# SCH_Smartlock-V3_2024-05-26.net
KiCad netlist of a schematic drawn in EasyEDA
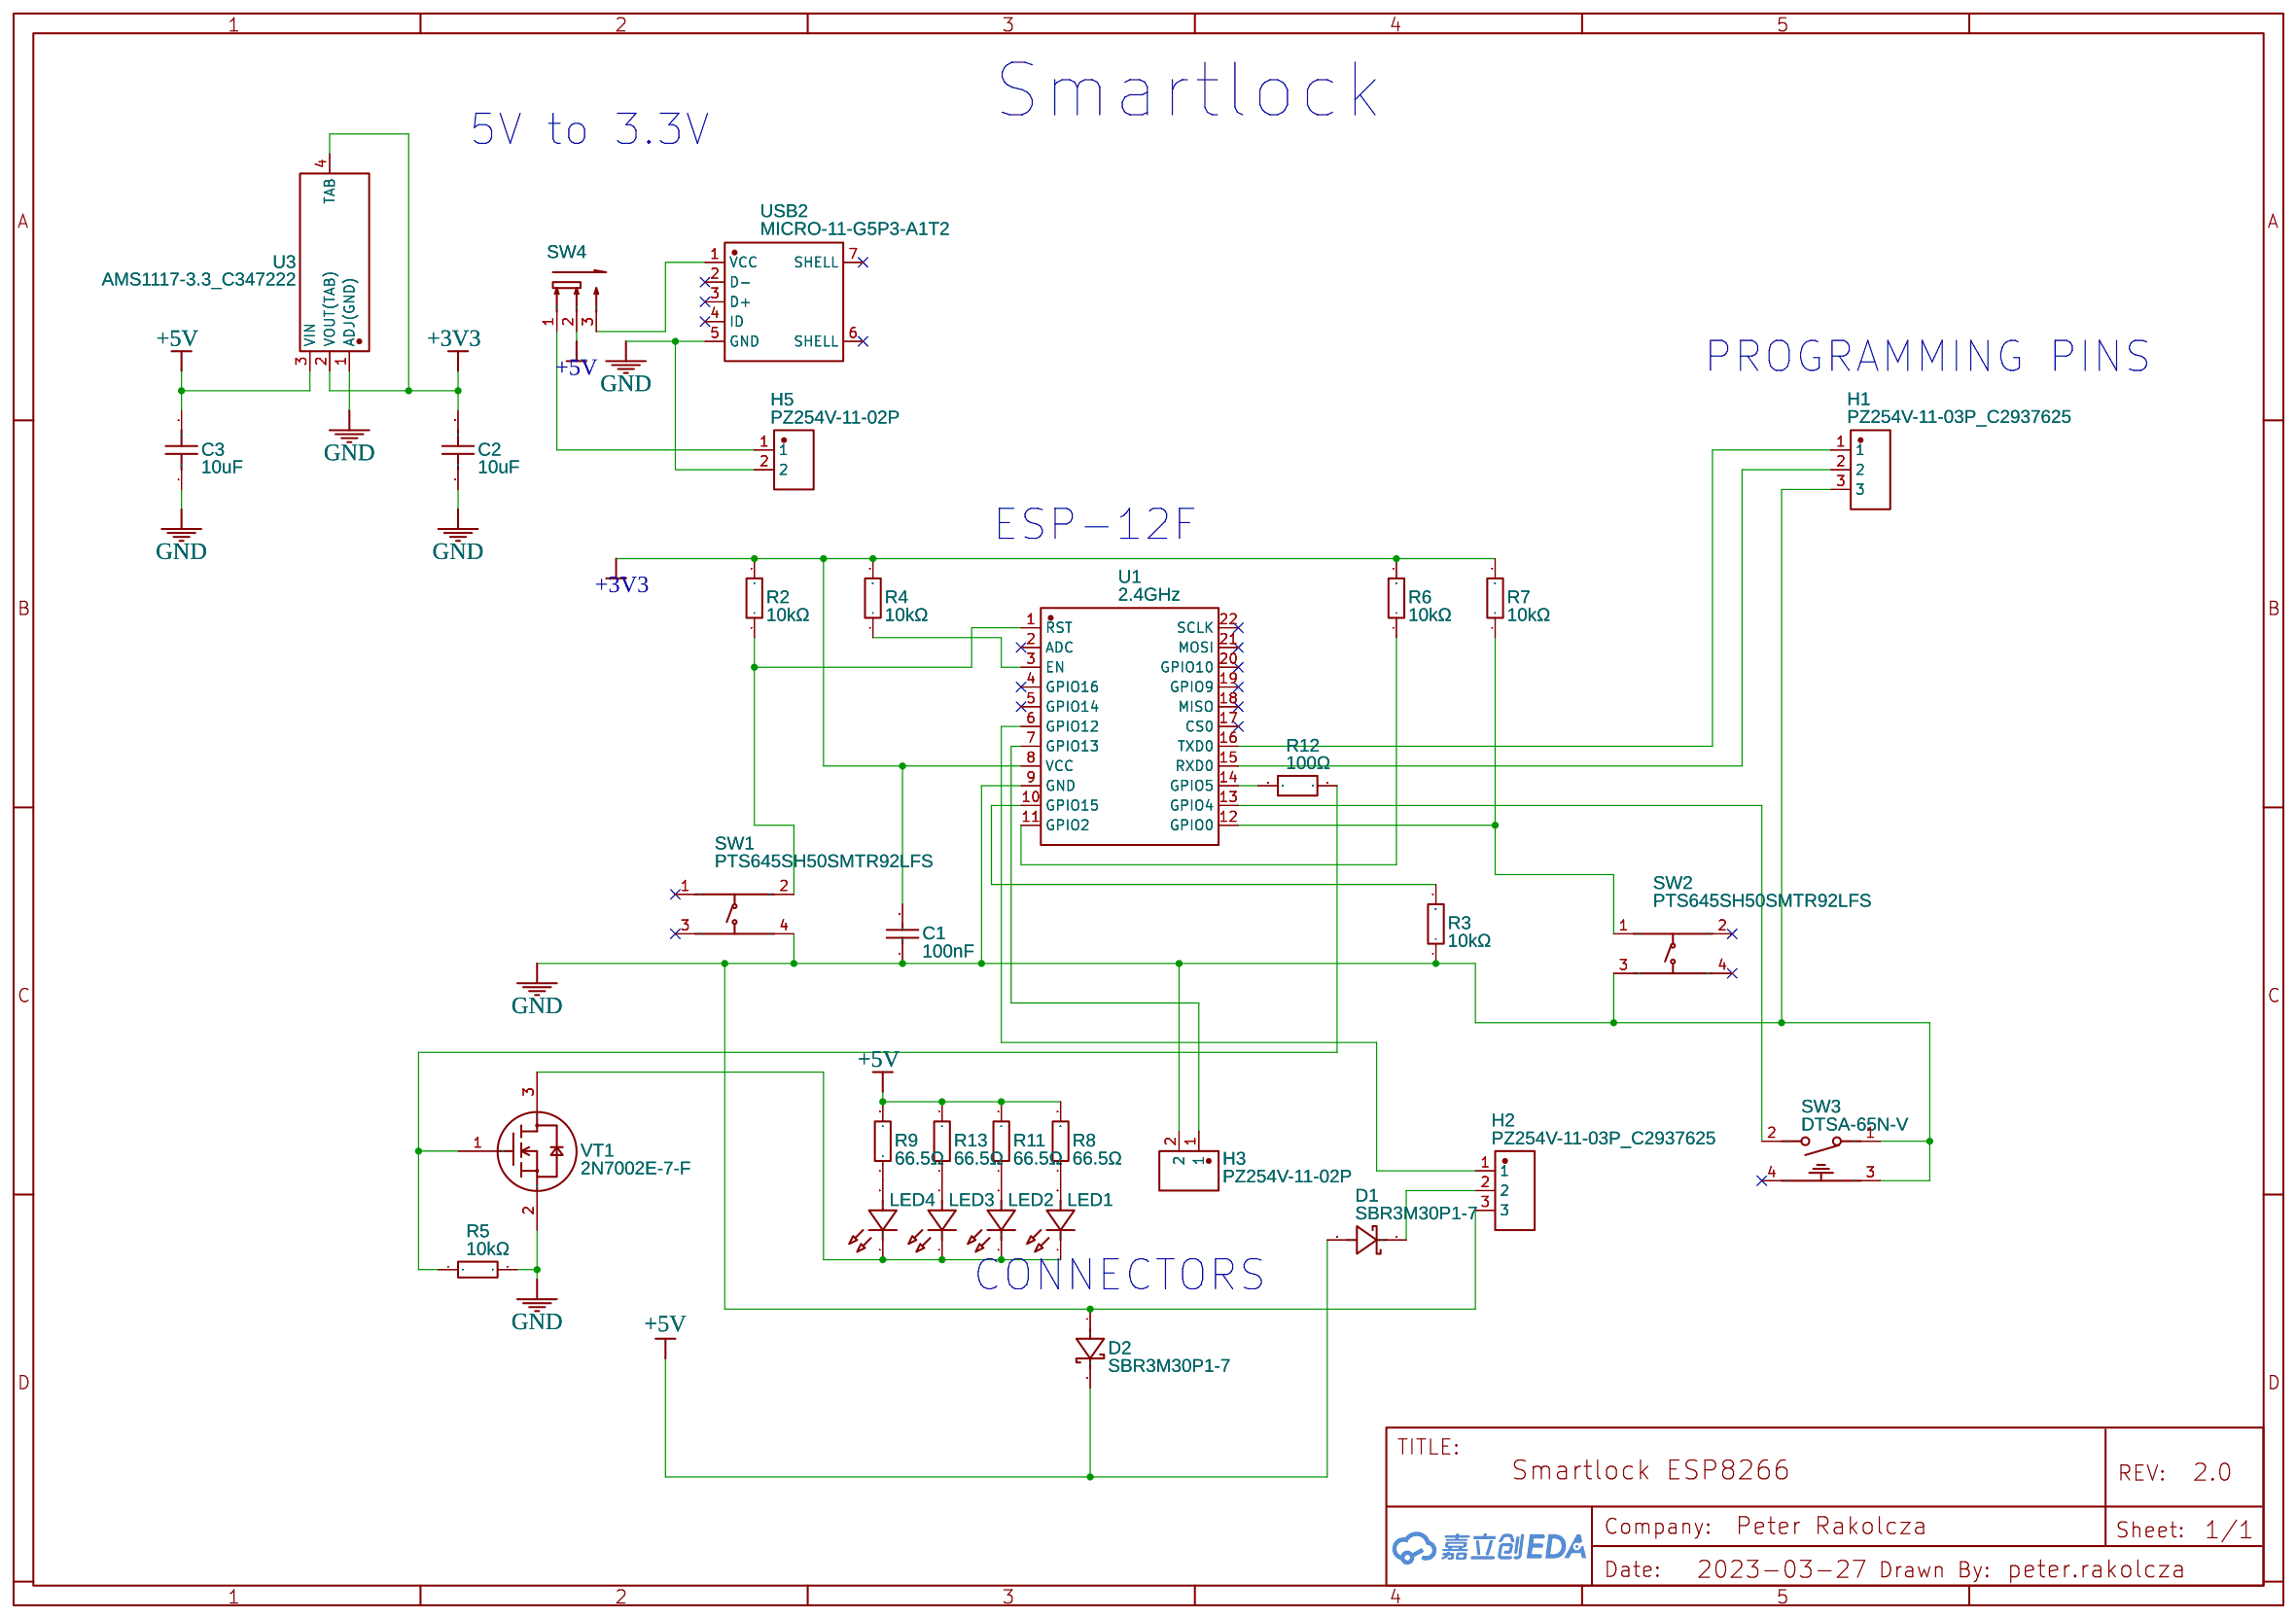
[diagram p0: schematic sheet]

(export (version "E")
  (design (tool "Eeschema 10.0.6"))
  (components
    (comp (ref "C1")
      (value "100nF")
      (fields
        (field (name "Manufacturer Part") "CL05B104KO5NNNC")
        (field (name "Manufacturer") "SAMSUNG(三星)")
      )
      (libsource (lib "") (part "CL05B104KO5NNNC"))
    )
    (comp (ref "C2")
      (value "10uF")
      (fields
        (field (name "Manufacturer Part") "CL05A106MP5NUNC")
        (field (name "Manufacturer") "Samsung Electro-Mechanics")
      )
      (libsource (lib "") (part "CL05A106MP5NUNC_C315248"))
    )
    (comp (ref "C3")
      (value "10uF")
      (fields
        (field (name "Manufacturer Part") "CL05A106MP5NUNC")
        (field (name "Manufacturer") "Samsung Electro-Mechanics")
      )
      (libsource (lib "") (part "CL05A106MP5NUNC_C315248"))
    )
    (comp (ref "D1")
      (value "SBR3M30P1-7")
      (fields (field (name "Manufacturer") "DIODES(美台)"))
      (libsource (lib "") (part "SBR3M30P1-7_1"))
    )
    (comp (ref "D2")
      (value "SBR3M30P1-7")
      (fields (field (name "Manufacturer") "DIODES(美台)"))
      (libsource (lib "") (part "SBR3M30P1-7"))
    )
    (comp (ref "H1")
      (value "PZ254V-11-03P_C2937625")
      (fields (field (name "Manufacturer Part") "PZ254V-11-03P") (field (name "Manufacturer") "XFCN(兴飞)"))
      (libsource (lib "") (part "PZ254V-11-03P_C2937625"))
    )
    (comp (ref "H2")
      (value "PZ254V-11-03P_C2937625")
      (fields (field (name "Manufacturer Part") "PZ254V-11-03P") (field (name "Manufacturer") "XFCN(兴飞)"))
      (libsource (lib "") (part "PZ254V-11-03P_C2937625"))
    )
    (comp (ref "H3")
      (value "PZ254V-11-02P")
      (fields (field (name "Manufacturer") "XFCN(兴飞)"))
      (libsource (lib "") (part "PZ254V-11-02P"))
    )
    (comp (ref "H5")
      (value "PZ254V-11-02P")
      (fields (field (name "Manufacturer") "XFCN(兴飞)"))
      (libsource (lib "") (part "PZ254V-11-02P_1"))
    )
    (comp (ref "LED1")
      (value "TZ-P2-0805WYCS2-0.8T")
      (fields (field (name "Manufacturer") "TUOZHAN(拓展光电)"))
      (libsource (lib "") (part "TZ-P2-0805WYCS2-0.8T"))
    )
    (comp (ref "LED2")
      (value "TZ-P2-0805WYCS2-0.8T")
      (fields (field (name "Manufacturer") "TUOZHAN(拓展光电)"))
      (libsource (lib "") (part "TZ-P2-0805WYCS2-0.8T"))
    )
    (comp (ref "LED3")
      (value "TZ-P2-0805WYCS2-0.8T")
      (fields (field (name "Manufacturer") "TUOZHAN(拓展光电)"))
      (libsource (lib "") (part "TZ-P2-0805WYCS2-0.8T"))
    )
    (comp (ref "LED4")
      (value "TZ-P2-0805WYCS2-0.8T")
      (fields (field (name "Manufacturer") "TUOZHAN(拓展光电)"))
      (libsource (lib "") (part "TZ-P2-0805WYCS2-0.8T"))
    )
    (comp (ref "R2")
      (value "10kΩ")
      (fields
        (field (name "Manufacturer Part") "0805W8F1002T5E")
        (field (name "Manufacturer") "UNI-ROYAL(厚声)")
      )
      (libsource (lib "") (part "0805W8F1002T5E"))
    )
    (comp (ref "R3")
      (value "10kΩ")
      (fields
        (field (name "Manufacturer Part") "0805W8F1002T5E")
        (field (name "Manufacturer") "UNI-ROYAL(厚声)")
      )
      (libsource (lib "") (part "0805W8F1002T5E"))
    )
    (comp (ref "R4")
      (value "10kΩ")
      (fields
        (field (name "Manufacturer Part") "0805W8F1002T5E")
        (field (name "Manufacturer") "UNI-ROYAL(厚声)")
      )
      (libsource (lib "") (part "0805W8F1002T5E"))
    )
    (comp (ref "R5")
      (value "10kΩ")
      (fields (field (name "Manufacturer Part") "RC0805FR-0710KL") (field (name "Manufacturer") "YAGEO(国巨)"))
      (libsource (lib "") (part "RC0805FR-0710KL"))
    )
    (comp (ref "R6")
      (value "10kΩ")
      (fields
        (field (name "Manufacturer Part") "0805W8F1002T5E")
        (field (name "Manufacturer") "UNI-ROYAL(厚声)")
      )
      (libsource (lib "") (part "0805W8F1002T5E"))
    )
    (comp (ref "R7")
      (value "10kΩ")
      (fields
        (field (name "Manufacturer Part") "0805W8F1002T5E")
        (field (name "Manufacturer") "UNI-ROYAL(厚声)")
      )
      (libsource (lib "") (part "0805W8F1002T5E"))
    )
    (comp (ref "R8")
      (value "66.5Ω")
      (fields (field (name "Manufacturer Part") "RS-05K66R5FT") (field (name "Manufacturer") "FH(风华)"))
      (libsource (lib "") (part "RS-05K66R5FT"))
    )
    (comp (ref "R9")
      (value "66.5Ω")
      (fields (field (name "Manufacturer Part") "RS-05K66R5FT") (field (name "Manufacturer") "FH(风华)"))
      (libsource (lib "") (part "RS-05K66R5FT"))
    )
    (comp (ref "R11")
      (value "66.5Ω")
      (fields (field (name "Manufacturer Part") "RS-05K66R5FT") (field (name "Manufacturer") "FH(风华)"))
      (libsource (lib "") (part "RS-05K66R5FT"))
    )
    (comp (ref "R12")
      (value "100Ω")
      (fields
        (field (name "Manufacturer Part") "CRCW0805100RJNEAC")
        (field (name "Manufacturer") "VISHAY(威世)")
      )
      (libsource (lib "") (part "CRCW0805100RJNEAC"))
    )
    (comp (ref "R13")
      (value "66.5Ω")
      (fields (field (name "Manufacturer Part") "RS-05K66R5FT") (field (name "Manufacturer") "FH(风华)"))
      (libsource (lib "") (part "RS-05K66R5FT"))
    )
    (comp (ref "SW1")
      (value "PTS645SH50SMTR92LFS")
      (fields (field (name "Manufacturer") "C&K"))
      (libsource (lib "") (part "PTS645SH50SMTR92LFS"))
    )
    (comp (ref "SW2")
      (value "PTS645SH50SMTR92LFS")
      (fields (field (name "Manufacturer") "C&K"))
      (libsource (lib "") (part "PTS645SH50SMTR92LFS"))
    )
    (comp (ref "SW3")
      (value "DTSA-65N-V")
      (fields (field (name "Manufacturer") "圜达"))
      (libsource (lib "") (part "DTSA-65N-V"))
    )
    (comp (ref "SW4")
      (value "MST-22D18G2 3J_C2875122")
      (fields
        (field (name "Manufacturer Part") "MST-22D18G2 3J")
        (field (name "Manufacturer") "SHOU HAN(首韩)")
      )
      (libsource (lib "") (part "MST-22D18G2 3J_C2875122"))
    )
    (comp (ref "U1")
      (value "2.4GHz")
      (fields
        (field (name "Manufacturer Part") "ESP-12F(ESP8266MOD)")
        (field (name "Manufacturer") "Ai-Thinker(安信可)")
      )
      (libsource (lib "") (part "ESP-12F(ESP8266MOD)"))
    )
    (comp (ref "U3")
      (value "AMS1117-3.3_C347222")
      (fields
        (field (name "Manufacturer Part") "AMS1117-3.3")
        (field (name "Manufacturer") "Youtai Semiconductor Co., Ltd.")
      )
      (libsource (lib "") (part "AMS1117-3.3_C347222"))
    )
    (comp (ref "USB2")
      (value "MICRO-11-G5P3-A1T2")
      (fields (field (name "Manufacturer") "Yuandi(台湾元迪)"))
      (libsource (lib "") (part "MICRO-11-G5P3-A1T2"))
    )
    (comp (ref "VT1")
      (value "2N7002E-7-F")
      (fields (field (name "Manufacturer") "DIODES(美台)"))
      (libsource (lib "") (part "2N7002E-7-F"))
    )
  )
  (nets
    (net (code "1") (name "+3V3") (class "Default")
      (node (ref "C1") (pin "2") (pinfunction "2_2") (pintype "input"))
      (node (ref "C2") (pin "2") (pinfunction "2_2") (pintype "unspecified"))
      (node (ref "R2") (pin "2") (pinfunction "2_2") (pintype "input"))
      (node (ref "R4") (pin "2") (pinfunction "2_2") (pintype "input"))
      (node (ref "R6") (pin "2") (pinfunction "2_2") (pintype "input"))
      (node (ref "R7") (pin "2") (pinfunction "2_2") (pintype "input"))
      (node (ref "U1") (pin "8") (pinfunction "VCC_8") (pintype "unspecified"))
      (node (ref "U3") (pin "2") (pinfunction "VOUT(TAB)_2") (pintype "unspecified"))
      (node (ref "U3") (pin "4") (pinfunction "TAB_4") (pintype "unspecified"))
    )
    (net (code "2") (name "+5V") (class "Default")
      (node (ref "C3") (pin "2") (pinfunction "2_2") (pintype "unspecified"))
      (node (ref "D1") (pin "1") (pinfunction "A_1") (pintype "unspecified"))
      (node (ref "D2") (pin "2") (pinfunction "K_2") (pintype "unspecified"))
      (node (ref "R11") (pin "2") (pinfunction "2_2") (pintype "unspecified"))
      (node (ref "R13") (pin "2") (pinfunction "2_2") (pintype "unspecified"))
      (node (ref "R8") (pin "2") (pinfunction "2_2") (pintype "unspecified"))
      (node (ref "R9") (pin "2") (pinfunction "2_2") (pintype "unspecified"))
      (node (ref "SW4") (pin "2") (pinfunction "2_2") (pintype "unspecified"))
      (node (ref "U3") (pin "3") (pinfunction "VIN_3") (pintype "unspecified"))
    )
    (net (code "3") (name "GND") (class "Default")
      (node (ref "C1") (pin "1") (pinfunction "1_1") (pintype "input"))
      (node (ref "C2") (pin "1") (pinfunction "1_1") (pintype "unspecified"))
      (node (ref "C3") (pin "1") (pinfunction "1_1") (pintype "unspecified"))
      (node (ref "D2") (pin "1") (pinfunction "A_1") (pintype "unspecified"))
      (node (ref "H1") (pin "3") (pinfunction "3_3") (pintype "unspecified"))
      (node (ref "H2") (pin "3") (pinfunction "3_3") (pintype "unspecified"))
      (node (ref "H3") (pin "2") (pinfunction "2_2") (pintype "unspecified"))
      (node (ref "H5") (pin "2") (pinfunction "2_2") (pintype "unspecified"))
      (node (ref "R3") (pin "1") (pinfunction "1_1") (pintype "input"))
      (node (ref "R5") (pin "2") (pinfunction "2_2") (pintype "input"))
      (node (ref "SW1") (pin "4") (pinfunction "4_4") (pintype "unspecified"))
      (node (ref "SW2") (pin "3") (pinfunction "3_3") (pintype "unspecified"))
      (node (ref "SW3") (pin "1") (pinfunction "1_1") (pintype "unspecified"))
      (node (ref "SW3") (pin "3") (pinfunction "3_3") (pintype "unspecified"))
      (node (ref "U1") (pin "9") (pinfunction "GND_9") (pintype "unspecified"))
      (node (ref "U3") (pin "1") (pinfunction "ADJ(GND)_1") (pintype "unspecified"))
      (node (ref "USB2") (pin "5") (pinfunction "GND_5") (pintype "unspecified"))
      (node (ref "VT1") (pin "2") (pinfunction "S_2") (pintype "unspecified"))
    )
    (net (code "4") (name "Net-(D1-K)") (class "Default")
      (node (ref "D1") (pin "2") (pinfunction "K_2") (pintype "unspecified"))
      (node (ref "H2") (pin "2") (pinfunction "2_2") (pintype "unspecified"))
    )
    (net (code "5") (name "Net-(H5-Pad1)") (class "Default")
      (node (ref "H5") (pin "1") (pinfunction "1_1") (pintype "unspecified"))
      (node (ref "SW4") (pin "1") (pinfunction "1_1") (pintype "unspecified"))
    )
    (net (code "6") (name "Net-(LED1-A)") (class "Default")
      (node (ref "LED1") (pin "2") (pinfunction "A_2") (pintype "unspecified"))
      (node (ref "R8") (pin "1") (pinfunction "1_1") (pintype "unspecified"))
    )
    (net (code "7") (name "Net-(LED1-K)") (class "Default")
      (node (ref "LED1") (pin "1") (pinfunction "K_1") (pintype "unspecified"))
      (node (ref "LED2") (pin "1") (pinfunction "K_1") (pintype "unspecified"))
      (node (ref "LED3") (pin "1") (pinfunction "K_1") (pintype "unspecified"))
      (node (ref "LED4") (pin "1") (pinfunction "K_1") (pintype "unspecified"))
      (node (ref "VT1") (pin "3") (pinfunction "D_3") (pintype "unspecified"))
    )
    (net (code "8") (name "Net-(LED2-A)") (class "Default")
      (node (ref "LED2") (pin "2") (pinfunction "A_2") (pintype "unspecified"))
      (node (ref "R11") (pin "1") (pinfunction "1_1") (pintype "unspecified"))
    )
    (net (code "9") (name "Net-(LED3-A)") (class "Default")
      (node (ref "LED3") (pin "2") (pinfunction "A_2") (pintype "unspecified"))
      (node (ref "R13") (pin "1") (pinfunction "1_1") (pintype "unspecified"))
    )
    (net (code "10") (name "Net-(LED4-A)") (class "Default")
      (node (ref "LED4") (pin "2") (pinfunction "A_2") (pintype "unspecified"))
      (node (ref "R9") (pin "1") (pinfunction "1_1") (pintype "unspecified"))
    )
    (net (code "11") (name "Net-(U1-EN)") (class "Default")
      (node (ref "R4") (pin "1") (pinfunction "1_1") (pintype "input"))
      (node (ref "U1") (pin "3") (pinfunction "EN_3") (pintype "unspecified"))
    )
    (net (code "12") (name "Net-(U1-GPIO0)") (class "Default")
      (node (ref "R7") (pin "1") (pinfunction "1_1") (pintype "input"))
      (node (ref "SW2") (pin "1") (pinfunction "1_1") (pintype "unspecified"))
      (node (ref "U1") (pin "12") (pinfunction "GPIO0_12") (pintype "unspecified"))
    )
    (net (code "13") (name "Net-(U1-GPIO2)") (class "Default")
      (node (ref "R6") (pin "1") (pinfunction "1_1") (pintype "input"))
      (node (ref "U1") (pin "11") (pinfunction "GPIO2_11") (pintype "unspecified"))
    )
    (net (code "14") (name "Net-(U1-GPIO4)") (class "Default")
      (node (ref "SW3") (pin "2") (pinfunction "2_2") (pintype "unspecified"))
      (node (ref "U1") (pin "13") (pinfunction "GPIO4_13") (pintype "unspecified"))
    )
    (net (code "15") (name "Net-(U1-GPIO5)") (class "Default")
      (node (ref "R12") (pin "1") (pinfunction "1_1") (pintype "unspecified"))
      (node (ref "U1") (pin "14") (pinfunction "GPIO5_14") (pintype "unspecified"))
    )
    (net (code "16") (name "Net-(U1-GPIO12)") (class "Default")
      (node (ref "H2") (pin "1") (pinfunction "1_1") (pintype "unspecified"))
      (node (ref "U1") (pin "6") (pinfunction "GPIO12_6") (pintype "unspecified"))
    )
    (net (code "17") (name "Net-(U1-GPIO13)") (class "Default")
      (node (ref "H3") (pin "1") (pinfunction "1_1") (pintype "unspecified"))
      (node (ref "U1") (pin "7") (pinfunction "GPIO13_7") (pintype "unspecified"))
    )
    (net (code "18") (name "Net-(U1-GPIO15)") (class "Default")
      (node (ref "R3") (pin "2") (pinfunction "2_2") (pintype "input"))
      (node (ref "U1") (pin "10") (pinfunction "GPIO15_10") (pintype "unspecified"))
    )
    (net (code "19") (name "Net-(U1-RST)") (class "Default")
      (node (ref "R2") (pin "1") (pinfunction "1_1") (pintype "input"))
      (node (ref "SW1") (pin "2") (pinfunction "2_2") (pintype "unspecified"))
      (node (ref "U1") (pin "1") (pinfunction "RST_1") (pintype "unspecified"))
    )
    (net (code "20") (name "Net-(U1-RXD0)") (class "Default")
      (node (ref "H1") (pin "2") (pinfunction "2_2") (pintype "unspecified"))
      (node (ref "U1") (pin "15") (pinfunction "RXD0_15") (pintype "unspecified"))
    )
    (net (code "21") (name "Net-(U1-TXD0)") (class "Default")
      (node (ref "H1") (pin "1") (pinfunction "1_1") (pintype "unspecified"))
      (node (ref "U1") (pin "16") (pinfunction "TXD0_16") (pintype "unspecified"))
    )
    (net (code "22") (name "Net-(USB2-VCC)") (class "Default")
      (node (ref "SW4") (pin "3") (pinfunction "3_3") (pintype "unspecified"))
      (node (ref "USB2") (pin "1") (pinfunction "VCC_1") (pintype "unspecified"))
    )
    (net (code "23") (name "Net-(VT1-G)") (class "Default")
      (node (ref "R12") (pin "2") (pinfunction "2_2") (pintype "unspecified"))
      (node (ref "R5") (pin "1") (pinfunction "1_1") (pintype "input"))
      (node (ref "VT1") (pin "1") (pinfunction "G_1") (pintype "unspecified"))
    )
    (net (code "24") (name "unconnected-(SW1-Pad1)") (class "Default")
      (node (ref "SW1") (pin "1") (pinfunction "1_1") (pintype "unspecified+no_connect"))
    )
    (net (code "25") (name "unconnected-(SW1-Pad3)") (class "Default")
      (node (ref "SW1") (pin "3") (pinfunction "3_3") (pintype "unspecified+no_connect"))
    )
    (net (code "26") (name "unconnected-(SW2-Pad2)") (class "Default")
      (node (ref "SW2") (pin "2") (pinfunction "2_2") (pintype "unspecified+no_connect"))
    )
    (net (code "27") (name "unconnected-(SW2-Pad4)") (class "Default")
      (node (ref "SW2") (pin "4") (pinfunction "4_4") (pintype "unspecified+no_connect"))
    )
    (net (code "28") (name "unconnected-(SW3-Pad4)") (class "Default")
      (node (ref "SW3") (pin "4") (pinfunction "4_4") (pintype "unspecified+no_connect"))
    )
    (net (code "29") (name "unconnected-(U1-ADC-Pad2)") (class "Default")
      (node (ref "U1") (pin "2") (pinfunction "ADC_2") (pintype "unspecified+no_connect"))
    )
    (net (code "30") (name "unconnected-(U1-CS0-Pad17)") (class "Default")
      (node (ref "U1") (pin "17") (pinfunction "CS0_17") (pintype "unspecified+no_connect"))
    )
    (net (code "31") (name "unconnected-(U1-GPIO9-Pad19)") (class "Default")
      (node (ref "U1") (pin "19") (pinfunction "GPIO9_19") (pintype "unspecified+no_connect"))
    )
    (net (code "32") (name "unconnected-(U1-GPIO10-Pad20)") (class "Default")
      (node (ref "U1") (pin "20") (pinfunction "GPIO10_20") (pintype "unspecified+no_connect"))
    )
    (net (code "33") (name "unconnected-(U1-GPIO14-Pad5)") (class "Default")
      (node (ref "U1") (pin "5") (pinfunction "GPIO14_5") (pintype "unspecified+no_connect"))
    )
    (net (code "34") (name "unconnected-(U1-GPIO16-Pad4)") (class "Default")
      (node (ref "U1") (pin "4") (pinfunction "GPIO16_4") (pintype "unspecified+no_connect"))
    )
    (net (code "35") (name "unconnected-(U1-MISO-Pad18)") (class "Default")
      (node (ref "U1") (pin "18") (pinfunction "MISO_18") (pintype "unspecified+no_connect"))
    )
    (net (code "36") (name "unconnected-(U1-MOSI-Pad21)") (class "Default")
      (node (ref "U1") (pin "21") (pinfunction "MOSI_21") (pintype "unspecified+no_connect"))
    )
    (net (code "37") (name "unconnected-(U1-SCLK-Pad22)") (class "Default")
      (node (ref "U1") (pin "22") (pinfunction "SCLK_22") (pintype "unspecified+no_connect"))
    )
    (net (code "38") (name "unconnected-(USB2-D+-Pad3)") (class "Default")
      (node (ref "USB2") (pin "3") (pinfunction "D+_3") (pintype "unspecified+no_connect"))
    )
    (net (code "39") (name "unconnected-(USB2-D--Pad2)") (class "Default")
      (node (ref "USB2") (pin "2") (pinfunction "D-_2") (pintype "unspecified+no_connect"))
    )
    (net (code "40") (name "unconnected-(USB2-ID-Pad4)") (class "Default")
      (node (ref "USB2") (pin "4") (pinfunction "ID_4") (pintype "unspecified+no_connect"))
    )
    (net (code "41") (name "unconnected-(USB2-SHELL-Pad6)") (class "Default")
      (node (ref "USB2") (pin "6") (pinfunction "SHELL_6") (pintype "unspecified+no_connect"))
    )
    (net (code "42") (name "unconnected-(USB2-SHELL-Pad7)") (class "Default")
      (node (ref "USB2") (pin "7") (pinfunction "SHELL_7") (pintype "unspecified+no_connect"))
    )
  )
)
